# Sheet1.net
KiCad netlist of a schematic drawn in Altium Designer
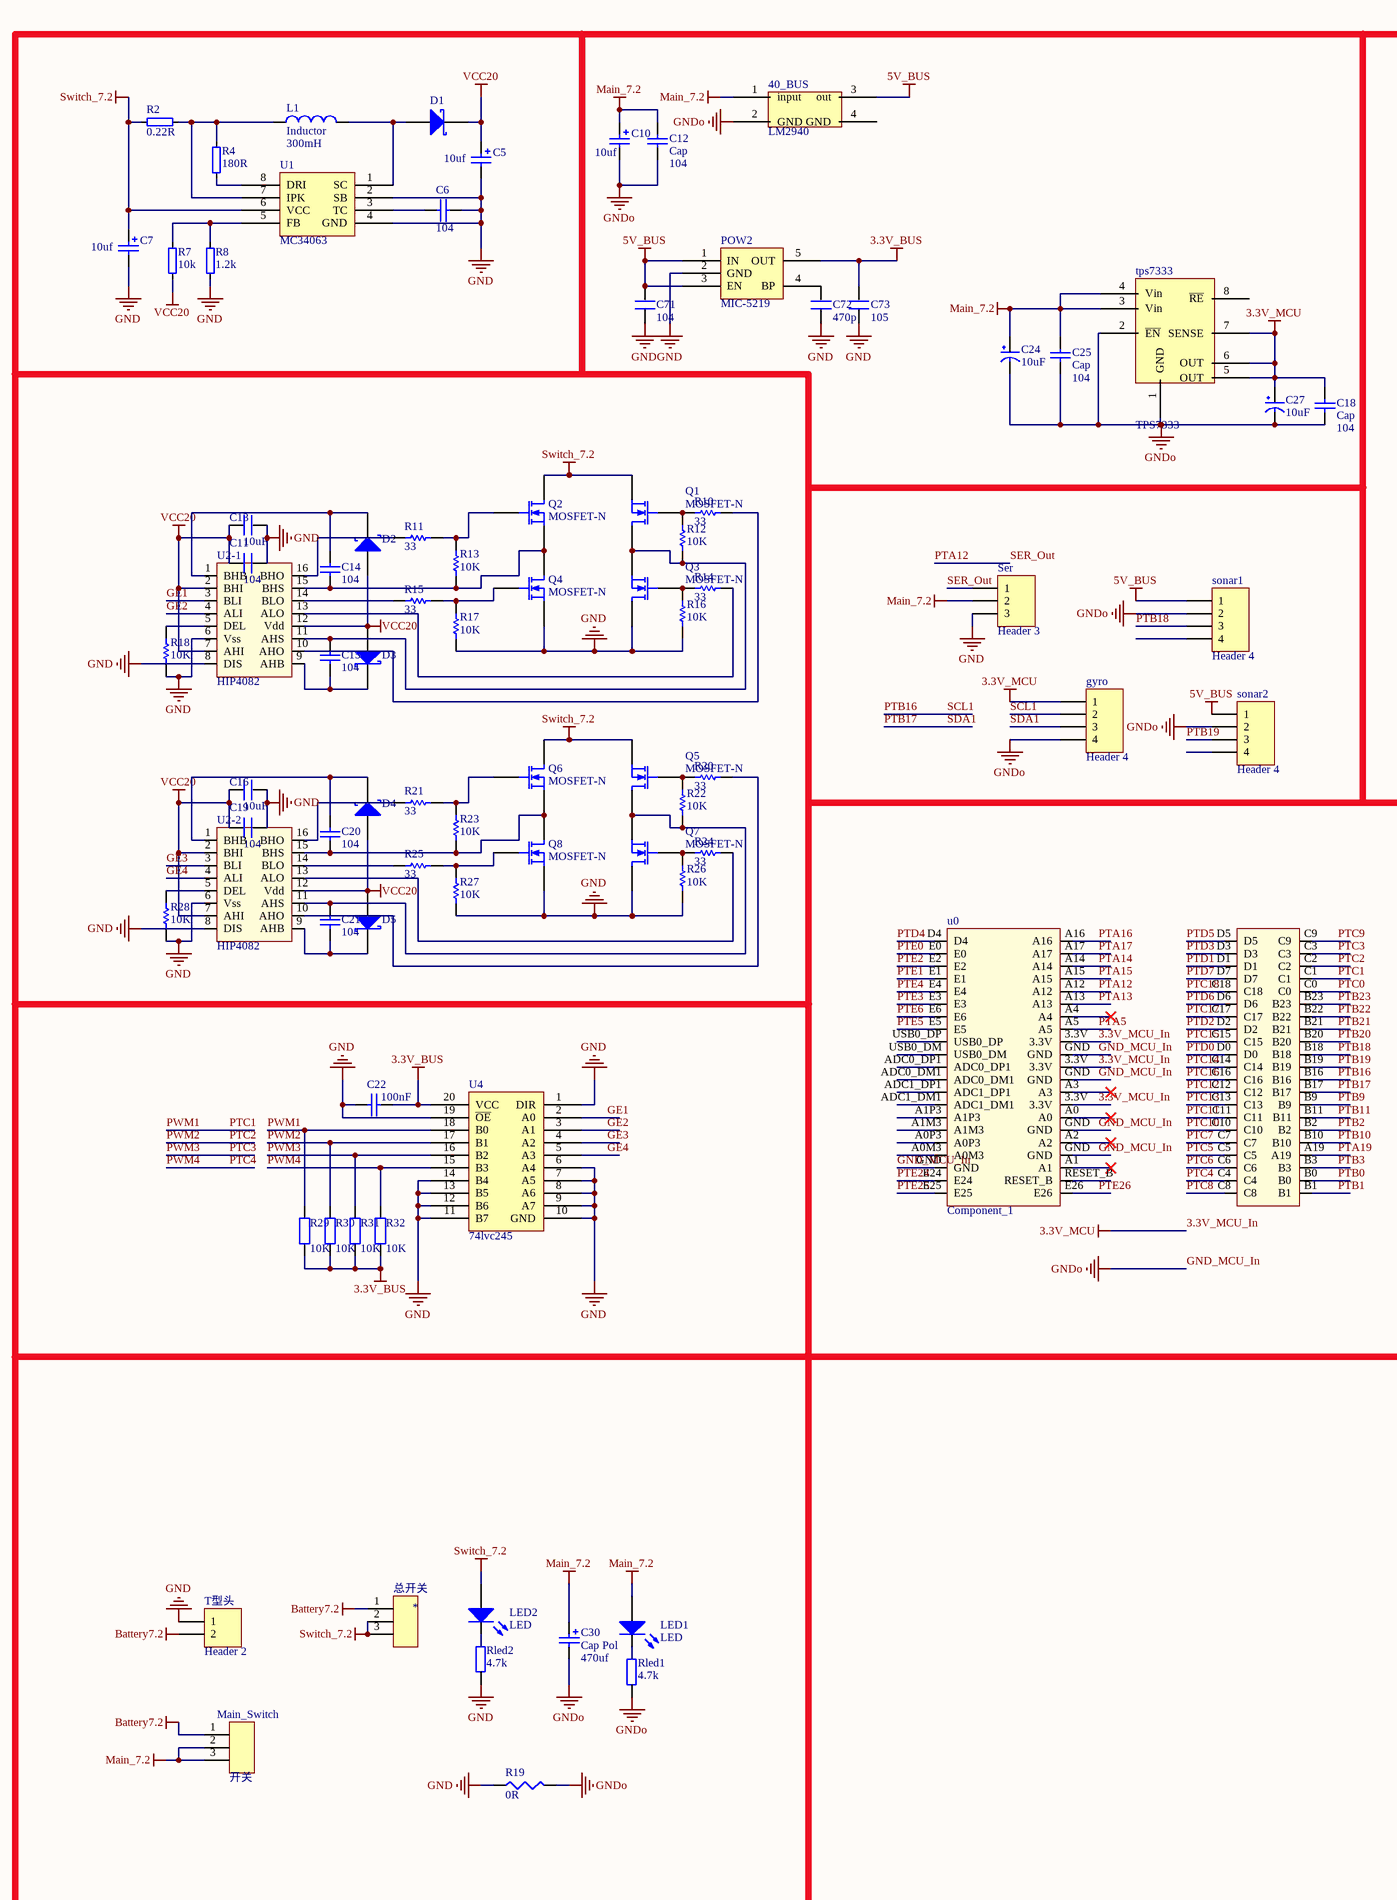
[diagram p0: Sheet1.SchDoc, left]
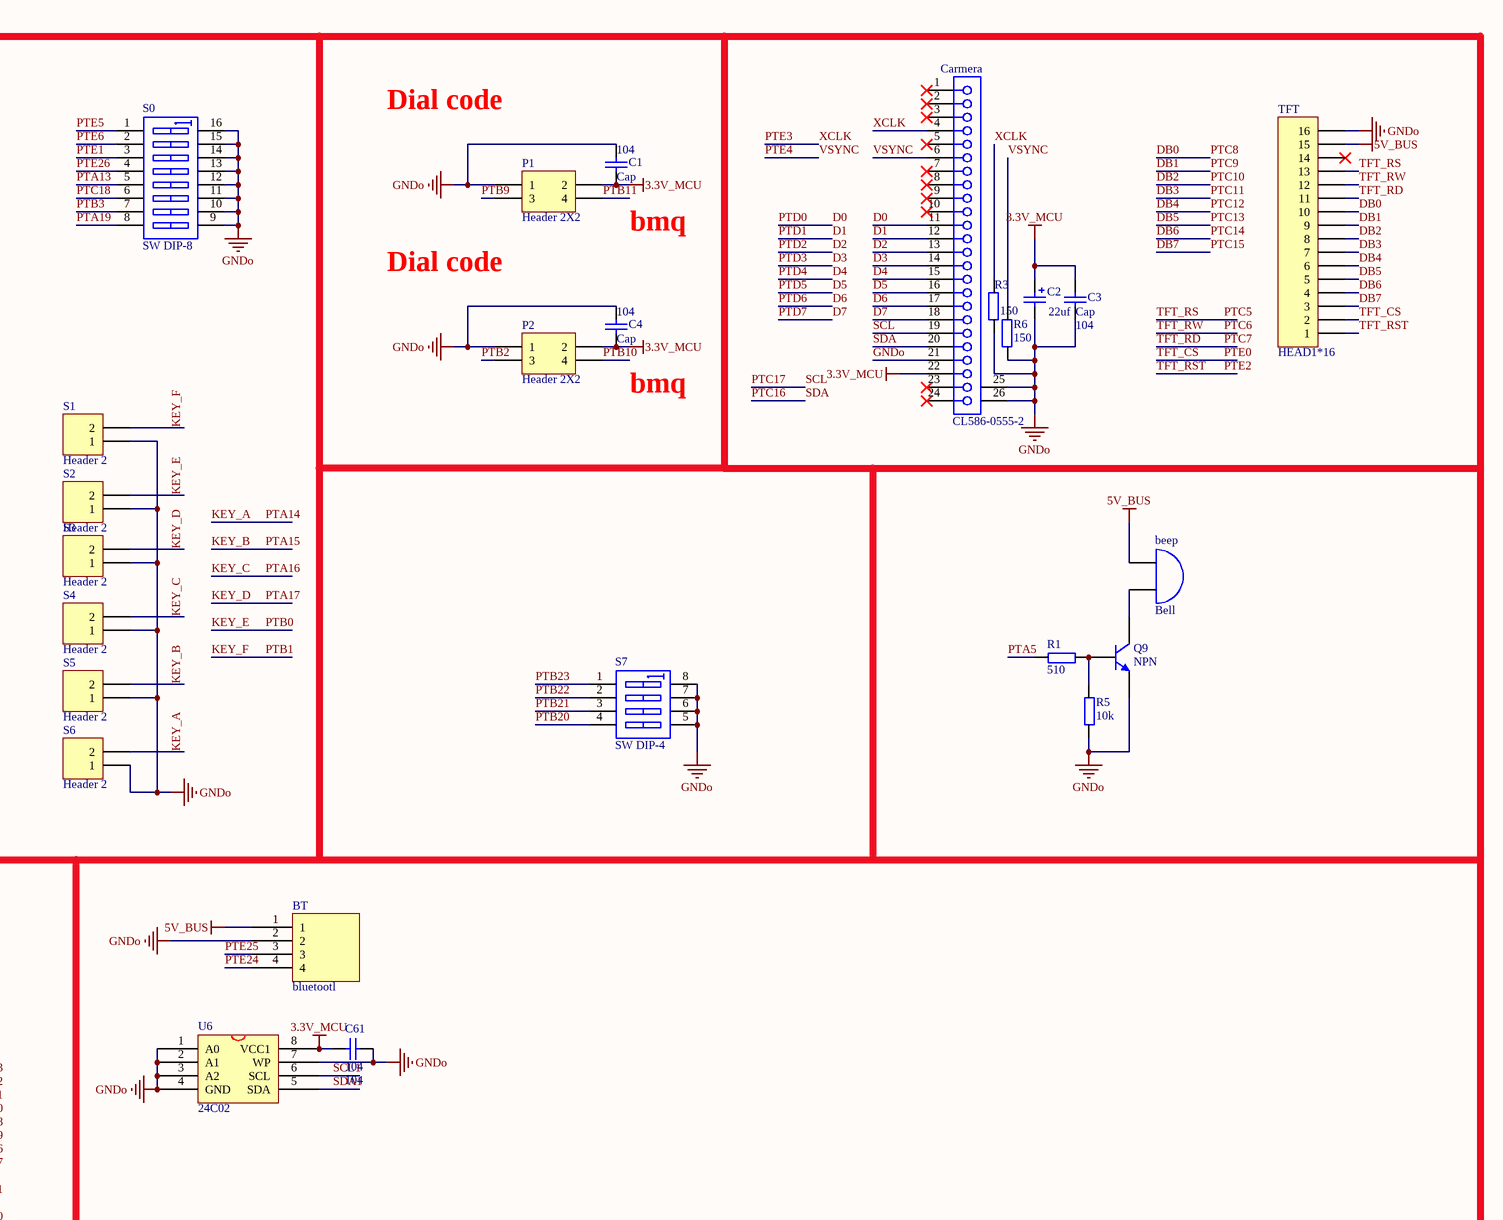
[diagram p1: Sheet1.SchDoc, right]

(export (version "E")
  (design (tool "Eeschema 10.0.6"))
  (components
    (comp (ref "40_BUS") (value "LM2940") (footprint "TO-263-3") (libsource (lib "常用元件") (part "LM2940")))
    (comp (ref "beep")
      (value "Bell")
      (footprint "bell")
      (description "Electrical Bell")
      (fields (field (name "PUBLISHER") "Altium Limited"))
      (libsource (lib "Miscellaneous Devices") (part "Bell"))
    )
    (comp (ref "BT")
      (value "bluetootl")
      (footprint "HDR1X4")
      (description "4 Pin Header")
      (libsource (lib "元件库") (part "USB"))
    )
    (comp (ref "C1")
      (value "Cap")
      (footprint "0805-0C")
      (description "Capacitor")
      (fields (field (name "ALTIUM_VALUE") "104") (field (name "PUBLISHER") "Altium Limited"))
      (libsource (lib "常用元件") (part "Cap"))
    )
    (comp (ref "C2")
      (value "22uf")
      (footprint "3216-A-TA")
      (description "Polarized Capacitor (Radial)")
      (fields (field (name "PUBLISHER") "Altium Limited"))
      (libsource (lib "常用元件") (part "Cap Pol"))
    )
    (comp (ref "C3")
      (value "Cap")
      (footprint "0805-0C")
      (description "Capacitor")
      (fields (field (name "ALTIUM_VALUE") "104") (field (name "PUBLISHER") "Altium Limited"))
      (libsource (lib "常用元件") (part "Cap"))
    )
    (comp (ref "C4")
      (value "Cap")
      (footprint "0805-0C")
      (description "Capacitor")
      (fields (field (name "ALTIUM_VALUE") "104") (field (name "PUBLISHER") "Altium Limited"))
      (libsource (lib "常用元件") (part "Cap"))
    )
    (comp (ref "C5")
      (value "10uf")
      (footprint "3216-A-TA")
      (description "Polarized Capacitor (Radial)")
      (fields (field (name "PUBLISHER") "Altium Limited"))
      (libsource (lib "常用元件") (part "Cap Pol"))
    )
    (comp (ref "C6")
      (value "104")
      (footprint "0805-0C")
      (description "Capacitor")
      (libsource (lib "电容") (part "普通电容"))
    )
    (comp (ref "C7")
      (value "10uf")
      (footprint "3216-A-TA")
      (description "Polarized Capacitor (Radial)")
      (fields (field (name "PUBLISHER") "Altium Limited"))
      (libsource (lib "常用元件") (part "Cap Pol"))
    )
    (comp (ref "C10")
      (value "10uf")
      (footprint "3216-A-TA")
      (description "Polarized Capacitor (Radial)")
      (fields (field (name "PUBLISHER") "Altium Limited"))
      (libsource (lib "常用元件") (part "Cap Pol"))
    )
    (comp (ref "C11") (value "104") (footprint "0805-0C") (libsource (lib "战舰STM32开发板底板封装库") (part "C")))
    (comp (ref "C12")
      (value "Cap")
      (footprint "0805-0C")
      (description "Capacitor")
      (fields (field (name "ALTIUM_VALUE") "104") (field (name "PUBLISHER") "Altium Limited"))
      (libsource (lib "常用元件") (part "Cap"))
    )
    (comp (ref "C13") (value "10uF") (footprint "3216-A-TA") (libsource (lib "战舰STM32开发板底板封装库") (part "C")))
    (comp (ref "C14")
      (value "104")
      (footprint "0805-0C")
      (description "Capacitor")
      (fields (field (name "Comment") "Cap") (field (name "PUBLISHER") "Altium Limited"))
      (libsource (lib "Miscellaneous Devices") (part "Cap"))
    )
    (comp (ref "C15")
      (value "104")
      (footprint "0805-0C")
      (description "Capacitor")
      (fields (field (name "Comment") "Cap") (field (name "PUBLISHER") "Altium Limited"))
      (libsource (lib "Miscellaneous Devices") (part "Cap"))
    )
    (comp (ref "C16") (value "10uF") (footprint "3216-A-TA") (libsource (lib "战舰STM32开发板底板封装库") (part "C")))
    (comp (ref "C18")
      (value "Cap")
      (footprint "0805-0C")
      (description "Capacitor")
      (fields (field (name "ALTIUM_VALUE") "104") (field (name "PUBLISHER") "Altium Limited"))
      (libsource (lib "常用元件") (part "Cap"))
    )
    (comp (ref "C19") (value "104") (footprint "0805-0C") (libsource (lib "战舰STM32开发板底板封装库") (part "C")))
    (comp (ref "C20")
      (value "104")
      (footprint "0805-0C")
      (description "Capacitor")
      (fields (field (name "Comment") "Cap") (field (name "PUBLISHER") "Altium Limited"))
      (libsource (lib "Miscellaneous Devices") (part "Cap"))
    )
    (comp (ref "C21")
      (value "104")
      (footprint "0805-0C")
      (description "Capacitor")
      (fields (field (name "Comment") "Cap") (field (name "PUBLISHER") "Altium Limited"))
      (libsource (lib "Miscellaneous Devices") (part "Cap"))
    )
    (comp (ref "C22")
      (value "100nF")
      (footprint "0603C")
      (description "Capacitor")
      (libsource (lib "MOS motor driving module ") (part "Cap"))
    )
    (comp (ref "C24")
      (value "10uF")
      (footprint "3216-A-TA")
      (description "有极性电容")
      (libsource (lib "原理图库") (part "C"))
    )
    (comp (ref "C25")
      (value "Cap")
      (footprint "0805-0C")
      (description "Capacitor")
      (fields (field (name "ALTIUM_VALUE") "104") (field (name "PUBLISHER") "Altium Limited"))
      (libsource (lib "常用元件集成库") (part "Cap"))
    )
    (comp (ref "C27")
      (value "10uF")
      (footprint "3216-A-TA")
      (description "有极性电容")
      (libsource (lib "原理图库") (part "C"))
    )
    (comp (ref "C30")
      (value "Cap Pol")
      (footprint "C7343")
      (description "Polarized Capacitor (Radial)")
      (fields (field (name "ALTIUM_VALUE") "470uf") (field (name "PUBLISHER") "Altium Limited"))
      (libsource (lib "常用元件") (part "Cap Pol"))
    )
    (comp (ref "C61")
      (value "104")
      (footprint "0603C")
      (description "Capacitor")
      (fields (field (name "ALTIUM_VALUE") "104") (field (name "PUBLISHER") "Altium Limited"))
      (libsource (lib "常用元件集成库") (part "Cap"))
    )
    (comp (ref "C71") (value "104") (footprint "0603P") (libsource (lib "战舰STM32开发板底板封装库") (part "C")))
    (comp (ref "C72") (value "470p") (footprint "0603P") (libsource (lib "战舰STM32开发板底板封装库") (part "C")))
    (comp (ref "C73") (value "105") (footprint "0603P") (libsource (lib "战舰STM32开发板底板封装库") (part "C")))
    (comp (ref "Carmera")
      (value "CL586-0555-2")
      (footprint "FH12A-24S-0.5SH")
      (description "FH12 Series, \"Flip-Lock\" SMT/ZIF FFC/FPC Connector - 0.5mm Spaced Top Contact")
      (fields (field (name "PUBLISHER") "Altium Limited"))
      (libsource (lib "HRS FPC-FFC FH12 Series") (part "CL586-0555-2"))
    )
    (comp (ref "D1")
      (value "D Schottky")
      (footprint "DO-214")
      (description "Schottky Diode")
      (fields (field (name "PUBLISHER") "Altium Limited"))
      (libsource (lib "Miscellaneous Devices") (part "D Schottky"))
    )
    (comp (ref "D2")
      (value "D Schottky")
      (footprint "DO-214")
      (description "Schottky Diode")
      (fields (field (name "PUBLISHER") "Altium Limited"))
      (libsource (lib "Miscellaneous Devices") (part "D Schottky"))
    )
    (comp (ref "D3")
      (value "D Schottky")
      (footprint "DO-214")
      (description "Schottky Diode")
      (fields (field (name "PUBLISHER") "Altium Limited"))
      (libsource (lib "Miscellaneous Devices") (part "D Schottky"))
    )
    (comp (ref "D4")
      (value "D Schottky")
      (footprint "DO-214")
      (description "Schottky Diode")
      (fields (field (name "PUBLISHER") "Altium Limited"))
      (libsource (lib "Miscellaneous Devices") (part "D Schottky"))
    )
    (comp (ref "D5")
      (value "D Schottky")
      (footprint "DO-214")
      (description "Schottky Diode")
      (fields (field (name "PUBLISHER") "Altium Limited"))
      (libsource (lib "Miscellaneous Devices") (part "D Schottky"))
    )
    (comp (ref "gyro")
      (value "Header 4")
      (footprint "HDR1X4")
      (description "Header, 4-Pin")
      (fields (field (name "PUBLISHER") "Altium Limited"))
      (libsource (lib "Miscellaneous Connectors") (part "Header 4"))
    )
    (comp (ref "L1")
      (value "Inductor")
      (footprint "L7X7")
      (fields (field (name "ALTIUM_VALUE") "300mH") (field (name "PUBLISHER") "Altium Limited"))
      (libsource (lib "Miscellaneous Devices") (part "Inductor"))
    )
    (comp (ref "LED1")
      (value "LED")
      (footprint "0805LED2")
      (description "发光二极管")
      (libsource (lib "原理图库") (part "LED"))
    )
    (comp (ref "LED2")
      (value "LED")
      (footprint "0805LED2")
      (description "发光二极管")
      (libsource (lib "原理图库") (part "LED"))
    )
    (comp (ref "Main_Switch") (value "开关") (footprint "乒乓开关5mm") (libsource (lib "常用元件集成库") (part "乒乓开关")))
    (comp (ref "P1")
      (value "Header 2X2")
      (footprint "HDR2X2")
      (description "Header, 2-Pin, Dual row")
      (fields (field (name "PUBLISHER") "Altium Limited"))
      (libsource (lib "Miscellaneous Connectors") (part "Header 2X2"))
    )
    (comp (ref "P2")
      (value "Header 2X2")
      (footprint "HDR2X2")
      (description "Header, 2-Pin, Dual row")
      (fields (field (name "PUBLISHER") "Altium Limited"))
      (libsource (lib "Miscellaneous Connectors") (part "Header 2X2"))
    )
    (comp (ref "POW2") (value "MIC-5219") (footprint "sot23-5") (libsource (lib "mic5219") (part "MIC-5219")))
    (comp (ref "Q1")
      (value "MOSFET-N")
      (footprint "to252")
      (description "N-Channel MOSFET")
      (fields (field (name "PUBLISHER") "Altium Limited"))
      (libsource (lib "Miscellaneous Devices") (part "MOSFET-N"))
    )
    (comp (ref "Q2")
      (value "MOSFET-N")
      (footprint "to252")
      (description "N-Channel MOSFET")
      (fields (field (name "PUBLISHER") "Altium Limited"))
      (libsource (lib "Miscellaneous Devices") (part "MOSFET-N"))
    )
    (comp (ref "Q3")
      (value "MOSFET-N")
      (footprint "to252")
      (description "N-Channel MOSFET")
      (fields (field (name "PUBLISHER") "Altium Limited"))
      (libsource (lib "Miscellaneous Devices") (part "MOSFET-N"))
    )
    (comp (ref "Q4")
      (value "MOSFET-N")
      (footprint "to252")
      (description "N-Channel MOSFET")
      (fields (field (name "PUBLISHER") "Altium Limited"))
      (libsource (lib "Miscellaneous Devices") (part "MOSFET-N"))
    )
    (comp (ref "Q5")
      (value "MOSFET-N")
      (footprint "to252")
      (description "N-Channel MOSFET")
      (fields (field (name "PUBLISHER") "Altium Limited"))
      (libsource (lib "Miscellaneous Devices") (part "MOSFET-N"))
    )
    (comp (ref "Q6")
      (value "MOSFET-N")
      (footprint "to252")
      (description "N-Channel MOSFET")
      (fields (field (name "PUBLISHER") "Altium Limited"))
      (libsource (lib "Miscellaneous Devices") (part "MOSFET-N"))
    )
    (comp (ref "Q7")
      (value "MOSFET-N")
      (footprint "to252")
      (description "N-Channel MOSFET")
      (fields (field (name "PUBLISHER") "Altium Limited"))
      (libsource (lib "Miscellaneous Devices") (part "MOSFET-N"))
    )
    (comp (ref "Q8")
      (value "MOSFET-N")
      (footprint "to252")
      (description "N-Channel MOSFET")
      (fields (field (name "PUBLISHER") "Altium Limited"))
      (libsource (lib "Miscellaneous Devices") (part "MOSFET-N"))
    )
    (comp (ref "Q9")
      (value "NPN")
      (footprint "TO-226-AA")
      (description "NPN Bipolar Transistor")
      (fields (field (name "PUBLISHER") "Altium Limited"))
      (libsource (lib "Miscellaneous Devices") (part "NPN"))
    )
    (comp (ref "R1") (value "510") (footprint "0805-0R") (libsource (lib "原理图库") (part "Res")))
    (comp (ref "R2") (value "0.22R") (footprint "0805-0R") (libsource (lib "电阻") (part "RES")))
    (comp (ref "R3") (value "150") (footprint "0805-0R") (libsource (lib "原理图库") (part "Res")))
    (comp (ref "R4") (value "180R") (footprint "0805-0R") (libsource (lib "电阻") (part "RES")))
    (comp (ref "R5") (value "10k") (footprint "0805-0r") (libsource (lib "原理图库") (part "Res")))
    (comp (ref "R6") (value "150") (footprint "0805-0R") (libsource (lib "原理图库") (part "Res")))
    (comp (ref "R7") (value "10k") (footprint "0805-0R") (libsource (lib "电阻") (part "RES")))
    (comp (ref "R8") (value "1.2k") (footprint "0805-0R") (libsource (lib "电阻") (part "RES")))
    (comp (ref "R10")
      (value "33")
      (footprint "0805-0R")
      (description "Resistor")
      (fields (field (name "Comment") "Res1") (field (name "PUBLISHER") "Altium Limited"))
      (libsource (lib "Miscellaneous Devices") (part "Res1"))
    )
    (comp (ref "R11")
      (value "33")
      (footprint "0805-0R")
      (description "Resistor")
      (fields (field (name "Comment") "Res1") (field (name "PUBLISHER") "Altium Limited"))
      (libsource (lib "Miscellaneous Devices") (part "Res1"))
    )
    (comp (ref "R12")
      (value "10K")
      (footprint "0805-0R")
      (description "Resistor")
      (fields (field (name "Comment") "Res1") (field (name "PUBLISHER") "Altium Limited"))
      (libsource (lib "Miscellaneous Devices") (part "Res1"))
    )
    (comp (ref "R13")
      (value "10K")
      (footprint "0805-0R")
      (description "Resistor")
      (fields (field (name "Comment") "Res1") (field (name "PUBLISHER") "Altium Limited"))
      (libsource (lib "Miscellaneous Devices") (part "Res1"))
    )
    (comp (ref "R14")
      (value "33")
      (footprint "0805-0R")
      (description "Resistor")
      (fields (field (name "Comment") "Res1") (field (name "PUBLISHER") "Altium Limited"))
      (libsource (lib "Miscellaneous Devices") (part "Res1"))
    )
    (comp (ref "R15")
      (value "33")
      (footprint "0805-0R")
      (description "Resistor")
      (fields (field (name "Comment") "Res1") (field (name "PUBLISHER") "Altium Limited"))
      (libsource (lib "Miscellaneous Devices") (part "Res1"))
    )
    (comp (ref "R16")
      (value "10K")
      (footprint "0805-0R")
      (description "Resistor")
      (fields (field (name "Comment") "Res1") (field (name "PUBLISHER") "Altium Limited"))
      (libsource (lib "Miscellaneous Devices") (part "Res1"))
    )
    (comp (ref "R17")
      (value "10K")
      (footprint "0805-0R")
      (description "Resistor")
      (fields (field (name "Comment") "Res1") (field (name "PUBLISHER") "Altium Limited"))
      (libsource (lib "Miscellaneous Devices") (part "Res1"))
    )
    (comp (ref "R18")
      (value "10K")
      (footprint "0805-0R")
      (description "Resistor")
      (fields (field (name "Comment") "Res1") (field (name "PUBLISHER") "Altium Limited"))
      (libsource (lib "Miscellaneous Devices") (part "Res1"))
    )
    (comp (ref "R19")
      (value "0R")
      (footprint "0805-0R")
      (description "Resistor")
      (fields (field (name "Comment") "Res") (field (name "PUBLISHER") "Altium Limited"))
      (libsource (lib "常用元件") (part "Res"))
    )
    (comp (ref "R20")
      (value "33")
      (footprint "0805-0R")
      (description "Resistor")
      (fields (field (name "Comment") "Res1") (field (name "PUBLISHER") "Altium Limited"))
      (libsource (lib "Miscellaneous Devices") (part "Res1"))
    )
    (comp (ref "R21")
      (value "33")
      (footprint "0805-0R")
      (description "Resistor")
      (fields (field (name "Comment") "Res1") (field (name "PUBLISHER") "Altium Limited"))
      (libsource (lib "Miscellaneous Devices") (part "Res1"))
    )
    (comp (ref "R22")
      (value "10K")
      (footprint "0805-0R")
      (description "Resistor")
      (fields (field (name "Comment") "Res1") (field (name "PUBLISHER") "Altium Limited"))
      (libsource (lib "Miscellaneous Devices") (part "Res1"))
    )
    (comp (ref "R23")
      (value "10K")
      (footprint "0805-0R")
      (description "Resistor")
      (fields (field (name "Comment") "Res1") (field (name "PUBLISHER") "Altium Limited"))
      (libsource (lib "Miscellaneous Devices") (part "Res1"))
    )
    (comp (ref "R24")
      (value "33")
      (footprint "0805-0R")
      (description "Resistor")
      (fields (field (name "Comment") "Res1") (field (name "PUBLISHER") "Altium Limited"))
      (libsource (lib "Miscellaneous Devices") (part "Res1"))
    )
    (comp (ref "R25")
      (value "33")
      (footprint "0805-0R")
      (description "Resistor")
      (fields (field (name "Comment") "Res1") (field (name "PUBLISHER") "Altium Limited"))
      (libsource (lib "Miscellaneous Devices") (part "Res1"))
    )
    (comp (ref "R26")
      (value "10K")
      (footprint "0805-0R")
      (description "Resistor")
      (fields (field (name "Comment") "Res1") (field (name "PUBLISHER") "Altium Limited"))
      (libsource (lib "Miscellaneous Devices") (part "Res1"))
    )
    (comp (ref "R27")
      (value "10K")
      (footprint "0805-0R")
      (description "Resistor")
      (fields (field (name "Comment") "Res1") (field (name "PUBLISHER") "Altium Limited"))
      (libsource (lib "Miscellaneous Devices") (part "Res1"))
    )
    (comp (ref "R28")
      (value "10K")
      (footprint "0805-0R")
      (description "Resistor")
      (fields (field (name "Comment") "Res1") (field (name "PUBLISHER") "Altium Limited"))
      (libsource (lib "Miscellaneous Devices") (part "Res1"))
    )
    (comp (ref "R29")
      (value "10K")
      (footprint "0603R")
      (description "Resistor")
      (fields (field (name "Comment") "Res2") (field (name "PUBLISHER") "Altium Limited"))
      (libsource (lib "MOS motor driving module ") (part "Res2"))
    )
    (comp (ref "R30")
      (value "10K")
      (footprint "0603R")
      (description "Resistor")
      (fields (field (name "Comment") "Res2") (field (name "PUBLISHER") "Altium Limited"))
      (libsource (lib "MOS motor driving module ") (part "Res2"))
    )
    (comp (ref "R31")
      (value "10K")
      (footprint "0603R")
      (description "Resistor")
      (fields (field (name "Comment") "Res2") (field (name "PUBLISHER") "Altium Limited"))
      (libsource (lib "MOS motor driving module ") (part "Res2"))
    )
    (comp (ref "R32")
      (value "10K")
      (footprint "0603R")
      (description "Resistor")
      (fields (field (name "Comment") "Res2") (field (name "PUBLISHER") "Altium Limited"))
      (libsource (lib "MOS motor driving module ") (part "Res2"))
    )
    (comp (ref "Rled1") (value "4.7k") (footprint "0805-0R") (libsource (lib "原理图库") (part "Res")))
    (comp (ref "Rled2") (value "4.7k") (footprint "0805-0R") (libsource (lib "原理图库") (part "Res")))
    (comp (ref "S0")
      (value "SW DIP-8")
      (footprint "SW-DIP8")
      (description "DIP Switch")
      (libsource (lib "元件库") (part "SW DIP-8"))
    )
    (comp (ref "S1")
      (value "Header 2")
      (footprint "SW-SMD1")
      (description "Header, 2-Pin")
      (fields (field (name "PUBLISHER") "Altium Limited"))
      (libsource (lib "Miscellaneous Connectors") (part "Header 2"))
    )
    (comp (ref "S2")
      (value "Header 2")
      (footprint "SW-SMD1")
      (description "Header, 2-Pin")
      (fields (field (name "PUBLISHER") "Altium Limited"))
      (libsource (lib "Miscellaneous Connectors") (part "Header 2"))
    )
    (comp (ref "S3")
      (value "Header 2")
      (footprint "SW-SMD1")
      (description "Header, 2-Pin")
      (fields (field (name "PUBLISHER") "Altium Limited"))
      (libsource (lib "Miscellaneous Connectors") (part "Header 2"))
    )
    (comp (ref "S4")
      (value "Header 2")
      (footprint "SW-SMD1")
      (description "Header, 2-Pin")
      (fields (field (name "PUBLISHER") "Altium Limited"))
      (libsource (lib "Miscellaneous Connectors") (part "Header 2"))
    )
    (comp (ref "S5")
      (value "Header 2")
      (footprint "SW-SMD1")
      (description "Header, 2-Pin")
      (fields (field (name "PUBLISHER") "Altium Limited"))
      (libsource (lib "Miscellaneous Connectors") (part "Header 2"))
    )
    (comp (ref "S6")
      (value "Header 2")
      (footprint "SW-SMD1")
      (description "Header, 2-Pin")
      (fields (field (name "PUBLISHER") "Altium Limited"))
      (libsource (lib "Miscellaneous Connectors") (part "Header 2"))
    )
    (comp (ref "S7")
      (value "SW DIP-4")
      (footprint "DIP-8")
      (description "DIP Switch")
      (libsource (lib "元件库") (part "SW DIP-4"))
    )
    (comp (ref "Ser")
      (value "Header 3")
      (footprint "HDR1X3")
      (description "Header, 3-Pin")
      (fields (field (name "PUBLISHER") "Altium Limited"))
      (libsource (lib "Miscellaneous Connectors") (part "Header 3"))
    )
    (comp (ref "sonar1")
      (value "Header 4")
      (footprint "HDR1X4")
      (description "Header, 4-Pin")
      (fields (field (name "PUBLISHER") "Altium Limited"))
      (libsource (lib "Miscellaneous Connectors") (part "Header 4"))
    )
    (comp (ref "sonar2")
      (value "Header 4")
      (footprint "HDR1X4")
      (description "Header, 4-Pin")
      (fields (field (name "PUBLISHER") "Altium Limited"))
      (libsource (lib "Miscellaneous Connectors") (part "Header 4"))
    )
    (comp (ref "TFT")
      (value "HEAD1*16")
      (footprint "HDR1X16")
      (description "Header, 16-Pin")
      (fields (field (name "PUBLISHER") "Altium Limited"))
      (libsource (lib "EXPLORER") (part "Header 16"))
    )
    (comp (ref "tps7333") (value "TPS7333") (footprint "sop8") (libsource (lib "常用元件") (part "TPS7333")))
    (comp (ref "T型头")
      (value "Header 2")
      (footprint "T HEAD")
      (description "Header, 2-Pin")
      (fields (field (name "PUBLISHER") "Altium Limited"))
      (libsource (lib "") (part "Header 2_1"))
    )
    (comp (ref "u0")
      (value "Component_1")
      (footprint "K60_100")
      (libsource (lib "K60_100") (part "Component_1"))
    )
    (comp (ref "U1") (value "MC34063") (footprint "sop8") (libsource (lib "MC34063") (part "Component_1")))
    (comp (ref "U2-1")
      (value "HIP4082")
      (footprint "SOP-16")
      (libsource (lib "HIP4082") (part "Component_1"))
    )
    (comp (ref "U2-2")
      (value "HIP4082")
      (footprint "SOP-16")
      (libsource (lib "HIP4082") (part "Component_1"))
    )
    (comp (ref "U4") (value "74lvc245") (footprint "TSSOP20") (libsource (lib "74lvc245") (part "74lvc245")))
    (comp (ref "U6") (value "24C02") (footprint "SOP8") (libsource (lib "EXPLORER") (part "24C256")))
    (comp (ref "总开关") (value "*") (footprint "乒乓开关5mm") (libsource (lib "常用元件集成库") (part "乒乓开关")))
  )
  (nets
    (net (code "1") (name "/D0") (class "Default")
      (node (ref "Carmera") (pin "11") (pinfunction "11_11") (pintype "passive"))
      (node (ref "u0") (pin "D0") (pinfunction "D0_D0") (pintype "passive"))
    )
    (net (code "2") (name "/D1") (class "Default")
      (node (ref "Carmera") (pin "12") (pinfunction "12_12") (pintype "passive"))
      (node (ref "u0") (pin "D1") (pinfunction "D1_D1") (pintype "passive"))
    )
    (net (code "3") (name "/D2") (class "Default")
      (node (ref "Carmera") (pin "13") (pinfunction "13_13") (pintype "passive"))
      (node (ref "u0") (pin "D2") (pinfunction "D2_D2") (pintype "passive"))
    )
    (net (code "4") (name "/D3") (class "Default")
      (node (ref "Carmera") (pin "14") (pinfunction "14_14") (pintype "passive"))
      (node (ref "u0") (pin "D3") (pinfunction "D3_D3") (pintype "passive"))
    )
    (net (code "5") (name "/D4") (class "Default")
      (node (ref "Carmera") (pin "15") (pinfunction "15_15") (pintype "passive"))
      (node (ref "u0") (pin "D4") (pinfunction "D4_D4") (pintype "passive"))
    )
    (net (code "6") (name "/D5") (class "Default")
      (node (ref "Carmera") (pin "16") (pinfunction "16_16") (pintype "passive"))
      (node (ref "u0") (pin "D5") (pinfunction "D5_D5") (pintype "passive"))
    )
    (net (code "7") (name "/D6") (class "Default")
      (node (ref "Carmera") (pin "17") (pinfunction "17_17") (pintype "passive"))
      (node (ref "u0") (pin "D6") (pinfunction "D6_D6") (pintype "passive"))
    )
    (net (code "8") (name "/D7") (class "Default")
      (node (ref "Carmera") (pin "18") (pinfunction "18_18") (pintype "passive"))
      (node (ref "u0") (pin "D7") (pinfunction "D7_D7") (pintype "passive"))
    )
    (net (code "9") (name "/DB0") (class "Default")
      (node (ref "TFT") (pin "10") (pinfunction "10_10") (pintype "passive"))
      (node (ref "u0") (pin "C8") (pinfunction "C8_C8") (pintype "passive"))
    )
    (net (code "10") (name "/DB1") (class "Default")
      (node (ref "TFT") (pin "9") (pinfunction "9_9") (pintype "passive"))
      (node (ref "u0") (pin "C9") (pinfunction "C9_C9") (pintype "passive"))
    )
    (net (code "11") (name "/DB2") (class "Default")
      (node (ref "TFT") (pin "8") (pinfunction "8_8") (pintype "passive"))
      (node (ref "u0") (pin "C10") (pinfunction "C10_C10") (pintype "passive"))
    )
    (net (code "12") (name "/DB3") (class "Default")
      (node (ref "TFT") (pin "7") (pinfunction "7_7") (pintype "passive"))
      (node (ref "u0") (pin "C11") (pinfunction "C11_C11") (pintype "passive"))
    )
    (net (code "13") (name "/DB4") (class "Default")
      (node (ref "TFT") (pin "6") (pinfunction "6_6") (pintype "passive"))
      (node (ref "u0") (pin "C12") (pinfunction "C12_C12") (pintype "passive"))
    )
    (net (code "14") (name "/DB5") (class "Default")
      (node (ref "TFT") (pin "5") (pinfunction "5_5") (pintype "passive"))
      (node (ref "u0") (pin "C13") (pinfunction "C13_C13") (pintype "passive"))
    )
    (net (code "15") (name "/DB6") (class "Default")
      (node (ref "TFT") (pin "4") (pinfunction "4_4") (pintype "passive"))
      (node (ref "u0") (pin "C14") (pinfunction "C14_C14") (pintype "passive"))
    )
    (net (code "16") (name "/DB7") (class "Default")
      (node (ref "TFT") (pin "3") (pinfunction "3_3") (pintype "passive"))
      (node (ref "u0") (pin "C15") (pinfunction "C15_C15") (pintype "passive"))
    )
    (net (code "17") (name "/GE1") (class "Default")
      (node (ref "U2-1") (pin "3") (pinfunction "BLI_3") (pintype "passive"))
      (node (ref "U4") (pin "2") (pinfunction "A0_2") (pintype "passive"))
    )
    (net (code "18") (name "/GE2") (class "Default")
      (node (ref "U2-1") (pin "4") (pinfunction "ALI_4") (pintype "passive"))
      (node (ref "U4") (pin "3") (pinfunction "A1_3") (pintype "passive"))
    )
    (net (code "19") (name "/GE3") (class "Default")
      (node (ref "U2-2") (pin "3") (pinfunction "BLI_3") (pintype "passive"))
      (node (ref "U4") (pin "4") (pinfunction "A2_4") (pintype "passive"))
    )
    (net (code "20") (name "/GE4") (class "Default")
      (node (ref "U2-2") (pin "4") (pinfunction "ALI_4") (pintype "passive"))
      (node (ref "U4") (pin "5") (pinfunction "A3_5") (pintype "passive"))
    )
    (net (code "21") (name "/KEY_A") (class "Default")
      (node (ref "S6") (pin "2") (pinfunction "2_2") (pintype "passive"))
      (node (ref "u0") (pin "A14") (pinfunction "A14_A14") (pintype "passive"))
    )
    (net (code "22") (name "/KEY_B") (class "Default")
      (node (ref "S5") (pin "2") (pinfunction "2_2") (pintype "passive"))
      (node (ref "u0") (pin "A15") (pinfunction "A15_A15") (pintype "passive"))
    )
    (net (code "23") (name "/KEY_C") (class "Default")
      (node (ref "S4") (pin "2") (pinfunction "2_2") (pintype "passive"))
      (node (ref "u0") (pin "A16") (pinfunction "A16_A16") (pintype "passive"))
    )
    (net (code "24") (name "/KEY_D") (class "Default")
      (node (ref "S3") (pin "2") (pinfunction "2_2") (pintype "passive"))
      (node (ref "u0") (pin "A17") (pinfunction "A17_A17") (pintype "passive"))
    )
    (net (code "25") (name "/KEY_E") (class "Default")
      (node (ref "S2") (pin "2") (pinfunction "2_2") (pintype "passive"))
      (node (ref "u0") (pin "B0") (pinfunction "B0_B0") (pintype "passive"))
    )
    (net (code "26") (name "/KEY_F") (class "Default")
      (node (ref "S1") (pin "2") (pinfunction "2_2") (pintype "passive"))
      (node (ref "u0") (pin "B1") (pinfunction "B1_B1") (pintype "passive"))
    )
    (net (code "27") (name "/PTA5") (class "Default")
      (node (ref "R1") (pin "1") (pintype "passive"))
      (node (ref "u0") (pin "A5") (pinfunction "A5_A5") (pintype "passive"))
    )
    (net (code "28") (name "/PTA12") (class "Default")
      (node (ref "Ser") (pin "1") (pinfunction "1_1") (pintype "passive"))
      (node (ref "u0") (pin "A12") (pinfunction "A12_A12") (pintype "passive"))
    )
    (net (code "29") (name "/PTA13") (class "Default")
      (node (ref "S0") (pin "5") (pinfunction "A5_5") (pintype "passive"))
      (node (ref "u0") (pin "A13") (pinfunction "A13_A13") (pintype "passive"))
    )
    (net (code "30") (name "/PTA19") (class "Default")
      (node (ref "S0") (pin "8") (pinfunction "A8_8") (pintype "passive"))
      (node (ref "u0") (pin "A19") (pinfunction "A19_A19") (pintype "passive"))
    )
    (net (code "31") (name "/PTB2") (class "Default")
      (node (ref "P2") (pin "3") (pinfunction "3_3") (pintype "passive"))
      (node (ref "u0") (pin "B2") (pinfunction "B2_B2") (pintype "passive"))
    )
    (net (code "32") (name "/PTB3") (class "Default")
      (node (ref "S0") (pin "7") (pinfunction "A7_7") (pintype "passive"))
      (node (ref "u0") (pin "B3") (pinfunction "B3_B3") (pintype "passive"))
    )
    (net (code "33") (name "/PTB9") (class "Default")
      (node (ref "P1") (pin "3") (pinfunction "3_3") (pintype "passive"))
      (node (ref "u0") (pin "B9") (pinfunction "B9_B9") (pintype "passive"))
    )
    (net (code "34") (name "/PTB10") (class "Default")
      (node (ref "P2") (pin "4") (pinfunction "4_4") (pintype "passive"))
      (node (ref "u0") (pin "B10") (pinfunction "B10_B10") (pintype "passive"))
    )
    (net (code "35") (name "/PTB11") (class "Default")
      (node (ref "P1") (pin "4") (pinfunction "4_4") (pintype "passive"))
      (node (ref "u0") (pin "B11") (pinfunction "B11_B11") (pintype "passive"))
    )
    (net (code "36") (name "/PTB16") (class "Default")
      (node (ref "U6") (pin "6") (pinfunction "SCL_6") (pintype "passive"))
      (node (ref "gyro") (pin "2") (pinfunction "2_2") (pintype "passive"))
      (node (ref "u0") (pin "B16") (pinfunction "B16_B16") (pintype "passive"))
    )
    (net (code "37") (name "/PTB17") (class "Default")
      (node (ref "U6") (pin "5") (pinfunction "SDA_5") (pintype "passive"))
      (node (ref "gyro") (pin "3") (pinfunction "3_3") (pintype "passive"))
      (node (ref "u0") (pin "B17") (pinfunction "B17_B17") (pintype "passive"))
    )
    (net (code "38") (name "/PTB18") (class "Default")
      (node (ref "sonar1") (pin "3") (pinfunction "3_3") (pintype "passive"))
      (node (ref "u0") (pin "B18") (pinfunction "B18_B18") (pintype "passive"))
    )
    (net (code "39") (name "/PTB19") (class "Default")
      (node (ref "sonar2") (pin "3") (pinfunction "3_3") (pintype "passive"))
      (node (ref "u0") (pin "B19") (pinfunction "B19_B19") (pintype "passive"))
    )
    (net (code "40") (name "/PTB20") (class "Default")
      (node (ref "S7") (pin "4") (pinfunction "A4_4") (pintype "passive"))
      (node (ref "u0") (pin "B20") (pinfunction "B20_B20") (pintype "passive"))
    )
    (net (code "41") (name "/PTB21") (class "Default")
      (node (ref "S7") (pin "3") (pinfunction "A3_3") (pintype "passive"))
      (node (ref "u0") (pin "B21") (pinfunction "B21_B21") (pintype "passive"))
    )
    (net (code "42") (name "/PTB22") (class "Default")
      (node (ref "S7") (pin "2") (pinfunction "A2_2") (pintype "passive"))
      (node (ref "u0") (pin "B22") (pinfunction "B22_B22") (pintype "passive"))
    )
    (net (code "43") (name "/PTB23") (class "Default")
      (node (ref "S7") (pin "1") (pinfunction "A1_1") (pintype "passive"))
      (node (ref "u0") (pin "B23") (pinfunction "B23_B23") (pintype "passive"))
    )
    (net (code "44") (name "/PTC0") (class "Default")
      (node (ref "u0") (pin "C0") (pinfunction "C0_C0") (pintype "passive"))
    )
    (net (code "45") (name "/PTC1") (class "Default")
      (node (ref "R29") (pin "2") (pinfunction "2_2") (pintype "passive"))
      (node (ref "U4") (pin "18") (pinfunction "B0_18") (pintype "passive"))
      (node (ref "u0") (pin "C1") (pinfunction "C1_C1") (pintype "passive"))
    )
    (net (code "46") (name "/PTC2") (class "Default")
      (node (ref "R30") (pin "2") (pinfunction "2_2") (pintype "passive"))
      (node (ref "U4") (pin "17") (pinfunction "B1_17") (pintype "passive"))
      (node (ref "u0") (pin "C2") (pinfunction "C2_C2") (pintype "passive"))
    )
    (net (code "47") (name "/PTC3") (class "Default")
      (node (ref "R31") (pin "2") (pinfunction "2_2") (pintype "passive"))
      (node (ref "U4") (pin "16") (pinfunction "B2_16") (pintype "passive"))
      (node (ref "u0") (pin "C3") (pinfunction "C3_C3") (pintype "passive"))
    )
    (net (code "48") (name "/PTC4") (class "Default")
      (node (ref "R32") (pin "2") (pinfunction "2_2") (pintype "passive"))
      (node (ref "U4") (pin "15") (pinfunction "B3_15") (pintype "passive"))
      (node (ref "u0") (pin "C4") (pinfunction "C4_C4") (pintype "passive"))
    )
    (net (code "49") (name "/PTC5") (class "Default")
      (node (ref "TFT") (pin "13") (pinfunction "13_13") (pintype "passive"))
      (node (ref "u0") (pin "C5") (pinfunction "C5_C5") (pintype "passive"))
    )
    (net (code "50") (name "/PTC6") (class "Default")
      (node (ref "TFT") (pin "12") (pinfunction "12_12") (pintype "passive"))
      (node (ref "u0") (pin "C6") (pinfunction "C6_C6") (pintype "passive"))
    )
    (net (code "51") (name "/PTC7") (class "Default")
      (node (ref "TFT") (pin "11") (pinfunction "11_11") (pintype "passive"))
      (node (ref "u0") (pin "C7") (pinfunction "C7_C7") (pintype "passive"))
    )
    (net (code "52") (name "/PTC16") (class "Default")
      (node (ref "Carmera") (pin "20") (pinfunction "20_20") (pintype "passive"))
      (node (ref "u0") (pin "C16") (pinfunction "C16_C16") (pintype "passive"))
    )
    (net (code "53") (name "/PTC17") (class "Default")
      (node (ref "Carmera") (pin "19") (pinfunction "19_19") (pintype "passive"))
      (node (ref "u0") (pin "C17") (pinfunction "C17_C17") (pintype "passive"))
    )
    (net (code "54") (name "/PTC18") (class "Default")
      (node (ref "S0") (pin "6") (pinfunction "A6_6") (pintype "passive"))
      (node (ref "u0") (pin "C18") (pinfunction "C18_C18") (pintype "passive"))
    )
    (net (code "55") (name "/PTE0") (class "Default")
      (node (ref "TFT") (pin "2") (pinfunction "2_2") (pintype "passive"))
      (node (ref "u0") (pin "E0") (pinfunction "E0_E0") (pintype "passive"))
    )
    (net (code "56") (name "/PTE1") (class "Default")
      (node (ref "S0") (pin "3") (pinfunction "A3_3") (pintype "passive"))
      (node (ref "u0") (pin "E1") (pinfunction "E1_E1") (pintype "passive"))
    )
    (net (code "57") (name "/PTE2") (class "Default")
      (node (ref "TFT") (pin "1") (pinfunction "1_1") (pintype "passive"))
      (node (ref "u0") (pin "E2") (pinfunction "E2_E2") (pintype "passive"))
    )
    (net (code "58") (name "/PTE3") (class "Default")
      (node (ref "Carmera") (pin "4") (pinfunction "4_4") (pintype "passive"))
      (node (ref "R3") (pin "1") (pintype "passive"))
      (node (ref "u0") (pin "E3") (pinfunction "E3_E3") (pintype "passive"))
    )
    (net (code "59") (name "/PTE4") (class "Default")
      (node (ref "Carmera") (pin "6") (pinfunction "6_6") (pintype "passive"))
      (node (ref "R6") (pin "1") (pintype "passive"))
      (node (ref "u0") (pin "E4") (pinfunction "E4_E4") (pintype "passive"))
    )
    (net (code "60") (name "/PTE5") (class "Default")
      (node (ref "S0") (pin "1") (pinfunction "A1_1") (pintype "passive"))
      (node (ref "u0") (pin "E5") (pinfunction "E5_E5") (pintype "passive"))
    )
    (net (code "61") (name "/PTE6") (class "Default")
      (node (ref "S0") (pin "2") (pinfunction "A2_2") (pintype "passive"))
      (node (ref "u0") (pin "E6") (pinfunction "E6_E6") (pintype "passive"))
    )
    (net (code "62") (name "/PTE24") (class "Default")
      (node (ref "BT") (pin "4") (pinfunction "4_4") (pintype "passive"))
      (node (ref "u0") (pin "E24") (pinfunction "E24_E24") (pintype "passive"))
    )
    (net (code "63") (name "/PTE25") (class "Default")
      (node (ref "BT") (pin "3") (pinfunction "3_3") (pintype "passive"))
      (node (ref "u0") (pin "E25") (pinfunction "E25_E25") (pintype "passive"))
    )
    (net (code "64") (name "/PTE26") (class "Default")
      (node (ref "S0") (pin "4") (pinfunction "A4_4") (pintype "passive"))
      (node (ref "u0") (pin "E26") (pinfunction "E26_E26") (pintype "passive"))
    )
    (net (code "65") (name "3.3V_BUS") (class "Default")
      (node (ref "C22") (pin "2") (pinfunction "2_2") (pintype "passive"))
      (node (ref "C73") (pin "2") (pintype "passive"))
      (node (ref "POW2") (pin "5") (pinfunction "OUT_5") (pintype "passive"))
      (node (ref "R29") (pin "1") (pinfunction "1_1") (pintype "passive"))
      (node (ref "R30") (pin "1") (pinfunction "1_1") (pintype "passive"))
      (node (ref "R31") (pin "1") (pinfunction "1_1") (pintype "passive"))
      (node (ref "R32") (pin "1") (pinfunction "1_1") (pintype "passive"))
      (node (ref "U4") (pin "20") (pinfunction "VCC_20") (pintype "passive"))
    )
    (net (code "66") (name "3.3V_MCU") (class "Default")
      (node (ref "C1") (pin "1") (pinfunction "1_1") (pintype "passive"))
      (node (ref "C18") (pin "2") (pinfunction "2_2") (pintype "passive"))
      (node (ref "C2") (pin "1") (pinfunction "1_1") (pintype "passive"))
      (node (ref "C27") (pin "1") (pinfunction "VCC_1") (pintype "passive"))
      (node (ref "C3") (pin "2") (pinfunction "2_2") (pintype "passive"))
      (node (ref "C4") (pin "1") (pinfunction "1_1") (pintype "passive"))
      (node (ref "C61") (pin "2") (pinfunction "2_2") (pintype "passive"))
      (node (ref "Carmera") (pin "22") (pinfunction "22_22") (pintype "passive"))
      (node (ref "P1") (pin "2") (pinfunction "2_2") (pintype "passive"))
      (node (ref "P2") (pin "2") (pinfunction "2_2") (pintype "passive"))
      (node (ref "U6") (pin "8") (pinfunction "VCC1_8") (pintype "passive"))
      (node (ref "gyro") (pin "1") (pinfunction "1_1") (pintype "passive"))
      (node (ref "tps7333") (pin "5") (pinfunction "OUT_5") (pintype "passive"))
      (node (ref "tps7333") (pin "6") (pinfunction "OUT_6") (pintype "passive"))
      (node (ref "tps7333") (pin "7") (pinfunction "SENSE_7") (pintype "passive"))
      (node (ref "u0") (pin "3.3V") (pinfunction "3.3V_3.3V") (pintype "passive"))
    )
    (net (code "67") (name "5V_BUS") (class "Default")
      (node (ref "40_BUS") (pin "3") (pinfunction "out_3") (pintype "passive"))
      (node (ref "BT") (pin "1") (pinfunction "1_1") (pintype "passive"))
      (node (ref "C71") (pin "2") (pintype "passive"))
      (node (ref "POW2") (pin "1") (pinfunction "IN_1") (pintype "passive"))
      (node (ref "POW2") (pin "3") (pinfunction "EN_3") (pintype "passive"))
      (node (ref "TFT") (pin "15") (pinfunction "15_15") (pintype "passive"))
      (node (ref "beep") (pin "1") (pinfunction "A_1") (pintype "passive"))
      (node (ref "sonar1") (pin "1") (pinfunction "1_1") (pintype "passive"))
      (node (ref "sonar2") (pin "1") (pinfunction "1_1") (pintype "passive"))
    )
    (net (code "68") (name "Battery7.2") (class "Default")
      (node (ref "Main_Switch") (pin "1") (pinfunction "16_1") (pintype "passive"))
      (node (ref "T型头") (pin "2") (pinfunction "2_2") (pintype "passive"))
      (node (ref "总开关") (pin "1") (pinfunction "16_1") (pintype "passive"))
    )
    (net (code "69") (name "GND") (class "Default")
      (node (ref "C11") (pin "1") (pintype "passive"))
      (node (ref "C13") (pin "1") (pintype "passive"))
      (node (ref "C16") (pin "1") (pintype "passive"))
      (node (ref "C19") (pin "1") (pintype "passive"))
      (node (ref "C22") (pin "1") (pinfunction "1_1") (pintype "passive"))
      (node (ref "C5") (pin "2") (pinfunction "2_2") (pintype "passive"))
      (node (ref "C6") (pin "2") (pinfunction "2_2") (pintype "passive"))
      (node (ref "C7") (pin "2") (pinfunction "2_2") (pintype "passive"))
      (node (ref "C71") (pin "1") (pintype "passive"))
      (node (ref "C72") (pin "1") (pintype "passive"))
      (node (ref "C73") (pin "1") (pintype "passive"))
      (node (ref "POW2") (pin "2") (pinfunction "GND_2") (pintype "passive"))
      (node (ref "Q3") (pin "1") (pinfunction "D_1") (pintype "passive"))
      (node (ref "Q4") (pin "3") (pinfunction "S_3") (pintype "passive"))
      (node (ref "Q7") (pin "1") (pinfunction "D_1") (pintype "passive"))
      (node (ref "Q8") (pin "3") (pinfunction "S_3") (pintype "passive"))
      (node (ref "R16") (pin "1") (pinfunction "1_1") (pintype "passive"))
      (node (ref "R17") (pin "1") (pinfunction "1_1") (pintype "passive"))
      (node (ref "R18") (pin "2") (pinfunction "2_2") (pintype "passive"))
      (node (ref "R19") (pin "1") (pinfunction "1_1") (pintype "passive"))
      (node (ref "R26") (pin "1") (pinfunction "1_1") (pintype "passive"))
      (node (ref "R27") (pin "1") (pinfunction "1_1") (pintype "passive"))
      (node (ref "R28") (pin "2") (pinfunction "2_2") (pintype "passive"))
      (node (ref "R8") (pin "1") (pinfunction "1_1") (pintype "passive"))
      (node (ref "Rled2") (pin "2") (pintype "passive"))
      (node (ref "Ser") (pin "3") (pinfunction "3_3") (pintype "passive"))
      (node (ref "T型头") (pin "1") (pinfunction "1_1") (pintype "passive"))
      (node (ref "U1") (pin "2") (pinfunction "SB_2") (pintype "passive"))
      (node (ref "U1") (pin "4") (pinfunction "GND_4") (pintype "passive"))
      (node (ref "U2-1") (pin "6") (pinfunction "Vss_6") (pintype "passive"))
      (node (ref "U2-1") (pin "8") (pinfunction "DIS_8") (pintype "passive"))
      (node (ref "U2-2") (pin "6") (pinfunction "Vss_6") (pintype "passive"))
      (node (ref "U2-2") (pin "8") (pinfunction "DIS_8") (pintype "passive"))
      (node (ref "U4") (pin "1") (pinfunction "DIR_1") (pintype "passive"))
      (node (ref "U4") (pin "10") (pinfunction "GND_10") (pintype "passive"))
      (node (ref "U4") (pin "11") (pinfunction "B7_11") (pintype "passive"))
      (node (ref "U4") (pin "12") (pinfunction "B6_12") (pintype "passive"))
      (node (ref "U4") (pin "13") (pinfunction "B5_13") (pintype "passive"))
      (node (ref "U4") (pin "14") (pinfunction "B4_14") (pintype "passive"))
      (node (ref "U4") (pin "19") (pinfunction "~{OE}_19") (pintype "passive"))
      (node (ref "U4") (pin "6") (pinfunction "A4_6") (pintype "passive"))
      (node (ref "U4") (pin "7") (pinfunction "A5_7") (pintype "passive"))
      (node (ref "U4") (pin "8") (pinfunction "A6_8") (pintype "passive"))
      (node (ref "U4") (pin "9") (pinfunction "A7_9") (pintype "passive"))
    )
    (net (code "70") (name "GNDo") (class "Default")
      (node (ref "40_BUS") (pin "2") (pinfunction "GND_2") (pintype "passive"))
      (node (ref "BT") (pin "2") (pinfunction "2_2") (pintype "passive"))
      (node (ref "C1") (pin "2") (pinfunction "2_2") (pintype "passive"))
      (node (ref "C10") (pin "2") (pinfunction "2_2") (pintype "passive"))
      (node (ref "C12") (pin "1") (pinfunction "1_1") (pintype "passive"))
      (node (ref "C18") (pin "1") (pinfunction "1_1") (pintype "passive"))
      (node (ref "C2") (pin "2") (pinfunction "2_2") (pintype "passive"))
      (node (ref "C24") (pin "2") (pinfunction "GND_2") (pintype "passive"))
      (node (ref "C25") (pin "1") (pinfunction "1_1") (pintype "passive"))
      (node (ref "C27") (pin "2") (pinfunction "GND_2") (pintype "passive"))
      (node (ref "C3") (pin "1") (pinfunction "1_1") (pintype "passive"))
      (node (ref "C30") (pin "2") (pinfunction "2_2") (pintype "passive"))
      (node (ref "C4") (pin "2") (pinfunction "2_2") (pintype "passive"))
      (node (ref "C61") (pin "1") (pinfunction "1_1") (pintype "passive"))
      (node (ref "Carmera") (pin "21") (pinfunction "21_21") (pintype "passive"))
      (node (ref "Carmera") (pin "25") (pinfunction "MH1_25") (pintype "passive"))
      (node (ref "Carmera") (pin "26") (pinfunction "MH2_26") (pintype "passive"))
      (node (ref "P1") (pin "1") (pinfunction "1_1") (pintype "passive"))
      (node (ref "P2") (pin "1") (pinfunction "1_1") (pintype "passive"))
      (node (ref "Q9") (pin "3") (pinfunction "E_3") (pintype "passive"))
      (node (ref "R19") (pin "2") (pinfunction "2_2") (pintype "passive"))
      (node (ref "R3") (pin "2") (pintype "passive"))
      (node (ref "R5") (pin "1") (pintype "passive"))
      (node (ref "R6") (pin "2") (pintype "passive"))
      (node (ref "Rled1") (pin "2") (pintype "passive"))
      (node (ref "S0") (pin "10") (pinfunction "B7_10") (pintype "passive"))
      (node (ref "S0") (pin "11") (pinfunction "B6_11") (pintype "passive"))
      (node (ref "S0") (pin "12") (pinfunction "B5_12") (pintype "passive"))
      (node (ref "S0") (pin "13") (pinfunction "B4_13") (pintype "passive"))
      (node (ref "S0") (pin "14") (pinfunction "B3_14") (pintype "passive"))
      (node (ref "S0") (pin "15") (pinfunction "B2_15") (pintype "passive"))
      (node (ref "S0") (pin "16") (pinfunction "B1_16") (pintype "passive"))
      (node (ref "S0") (pin "9") (pinfunction "B8_9") (pintype "passive"))
      (node (ref "S1") (pin "1") (pinfunction "1_1") (pintype "passive"))
      (node (ref "S2") (pin "1") (pinfunction "1_1") (pintype "passive"))
      (node (ref "S3") (pin "1") (pinfunction "1_1") (pintype "passive"))
      (node (ref "S4") (pin "1") (pinfunction "1_1") (pintype "passive"))
      (node (ref "S5") (pin "1") (pinfunction "1_1") (pintype "passive"))
      (node (ref "S6") (pin "1") (pinfunction "1_1") (pintype "passive"))
      (node (ref "S7") (pin "5") (pinfunction "B4_5") (pintype "passive"))
      (node (ref "S7") (pin "6") (pinfunction "B3_6") (pintype "passive"))
      (node (ref "S7") (pin "7") (pinfunction "B2_7") (pintype "passive"))
      (node (ref "S7") (pin "8") (pinfunction "B1_8") (pintype "passive"))
      (node (ref "TFT") (pin "16") (pinfunction "16_16") (pintype "passive"))
      (node (ref "U6") (pin "1") (pinfunction "A0_1") (pintype "passive"))
      (node (ref "U6") (pin "2") (pinfunction "A1_2") (pintype "passive"))
      (node (ref "U6") (pin "3") (pinfunction "A2_3") (pintype "passive"))
      (node (ref "U6") (pin "4") (pinfunction "GND_4") (pintype "passive"))
      (node (ref "U6") (pin "7") (pinfunction "WP_7") (pintype "passive"))
      (node (ref "gyro") (pin "4") (pinfunction "4_4") (pintype "passive"))
      (node (ref "sonar1") (pin "2") (pinfunction "2_2") (pintype "passive"))
      (node (ref "sonar2") (pin "2") (pinfunction "2_2") (pintype "passive"))
      (node (ref "tps7333") (pin "1") (pinfunction "GND_1") (pintype "passive"))
      (node (ref "tps7333") (pin "2") (pinfunction "~{EN}_2") (pintype "passive"))
      (node (ref "u0") (pin "GND") (pinfunction "GND_GND") (pintype "passive"))
    )
    (net (code "71") (name "Main_7.2") (class "Default")
      (node (ref "40_BUS") (pin "1") (pinfunction "input_1") (pintype "passive"))
      (node (ref "C10") (pin "1") (pinfunction "1_1") (pintype "passive"))
      (node (ref "C12") (pin "2") (pinfunction "2_2") (pintype "passive"))
      (node (ref "C24") (pin "1") (pinfunction "VCC_1") (pintype "passive"))
      (node (ref "C25") (pin "2") (pinfunction "2_2") (pintype "passive"))
      (node (ref "C30") (pin "1") (pinfunction "1_1") (pintype "passive"))
      (node (ref "LED1") (pin "1") (pinfunction "A_1") (pintype "passive"))
      (node (ref "Main_Switch") (pin "2") (pinfunction "17_2") (pintype "passive"))
      (node (ref "Main_Switch") (pin "3") (pinfunction "18_3") (pintype "passive"))
      (node (ref "Ser") (pin "2") (pinfunction "2_2") (pintype "passive"))
      (node (ref "tps7333") (pin "3") (pinfunction "Vin_3") (pintype "passive"))
      (node (ref "tps7333") (pin "4") (pinfunction "Vin_4") (pintype "passive"))
    )
    (net (code "72") (name "Net-(D1-A)") (class "Default")
      (node (ref "D1") (pin "1") (pinfunction "A_1") (pintype "passive"))
      (node (ref "L1") (pin "2") (pinfunction "2_2") (pintype "passive"))
      (node (ref "U1") (pin "1") (pinfunction "SC_1") (pintype "passive"))
    )
    (net (code "73") (name "Net-(D2-K)") (class "Default")
      (node (ref "C14") (pin "2") (pinfunction "2_2") (pintype "passive"))
      (node (ref "D2") (pin "2") (pinfunction "K_2") (pintype "passive"))
      (node (ref "U2-1") (pin "1") (pinfunction "BHB_1") (pintype "passive"))
    )
    (net (code "74") (name "Net-(D3-K)") (class "Default")
      (node (ref "C15") (pin "2") (pinfunction "2_2") (pintype "passive"))
      (node (ref "D3") (pin "2") (pinfunction "K_2") (pintype "passive"))
      (node (ref "U2-1") (pin "9") (pinfunction "AHB_9") (pintype "passive"))
    )
    (net (code "75") (name "Net-(D4-K)") (class "Default")
      (node (ref "C20") (pin "2") (pinfunction "2_2") (pintype "passive"))
      (node (ref "D4") (pin "2") (pinfunction "K_2") (pintype "passive"))
      (node (ref "U2-2") (pin "1") (pinfunction "BHB_1") (pintype "passive"))
    )
    (net (code "76") (name "Net-(D5-K)") (class "Default")
      (node (ref "C21") (pin "2") (pinfunction "2_2") (pintype "passive"))
      (node (ref "D5") (pin "2") (pinfunction "K_2") (pintype "passive"))
      (node (ref "U2-2") (pin "9") (pinfunction "AHB_9") (pintype "passive"))
    )
    (net (code "77") (name "Net-(LED1-K)") (class "Default")
      (node (ref "LED1") (pin "2") (pinfunction "K_2") (pintype "passive"))
      (node (ref "Rled1") (pin "1") (pintype "passive"))
    )
    (net (code "78") (name "Net-(LED2-K)") (class "Default")
      (node (ref "LED2") (pin "2") (pinfunction "K_2") (pintype "passive"))
      (node (ref "Rled2") (pin "1") (pintype "passive"))
    )
    (net (code "79") (name "Net-(POW2-BP)") (class "Default")
      (node (ref "C72") (pin "2") (pintype "passive"))
      (node (ref "POW2") (pin "4") (pinfunction "BP_4") (pintype "passive"))
    )
    (net (code "80") (name "Net-(Q1-D)") (class "Default")
      (node (ref "C15") (pin "1") (pinfunction "1_1") (pintype "passive"))
      (node (ref "Q1") (pin "1") (pinfunction "D_1") (pintype "passive"))
      (node (ref "Q3") (pin "3") (pinfunction "S_3") (pintype "passive"))
      (node (ref "R12") (pin "1") (pinfunction "1_1") (pintype "passive"))
      (node (ref "U2-1") (pin "11") (pinfunction "AHS_11") (pintype "passive"))
    )
    (net (code "81") (name "Net-(Q1-G)") (class "Default")
      (node (ref "Q1") (pin "2") (pinfunction "G_2") (pintype "passive"))
      (node (ref "R10") (pin "1") (pinfunction "1_1") (pintype "passive"))
      (node (ref "R12") (pin "2") (pinfunction "2_2") (pintype "passive"))
    )
    (net (code "82") (name "Net-(Q2-G)") (class "Default")
      (node (ref "Q2") (pin "2") (pinfunction "G_2") (pintype "passive"))
      (node (ref "R11") (pin "2") (pinfunction "2_2") (pintype "passive"))
      (node (ref "R13") (pin "2") (pinfunction "2_2") (pintype "passive"))
    )
    (net (code "83") (name "Net-(Q2-S)") (class "Default")
      (node (ref "C14") (pin "1") (pinfunction "1_1") (pintype "passive"))
      (node (ref "Q2") (pin "3") (pinfunction "S_3") (pintype "passive"))
      (node (ref "Q4") (pin "1") (pinfunction "D_1") (pintype "passive"))
      (node (ref "R13") (pin "1") (pinfunction "1_1") (pintype "passive"))
      (node (ref "U2-1") (pin "15") (pinfunction "BHS_15") (pintype "passive"))
    )
    (net (code "84") (name "Net-(Q3-G)") (class "Default")
      (node (ref "Q3") (pin "2") (pinfunction "G_2") (pintype "passive"))
      (node (ref "R14") (pin "1") (pinfunction "1_1") (pintype "passive"))
      (node (ref "R16") (pin "2") (pinfunction "2_2") (pintype "passive"))
    )
    (net (code "85") (name "Net-(Q4-G)") (class "Default")
      (node (ref "Q4") (pin "2") (pinfunction "G_2") (pintype "passive"))
      (node (ref "R15") (pin "2") (pinfunction "2_2") (pintype "passive"))
      (node (ref "R17") (pin "2") (pinfunction "2_2") (pintype "passive"))
    )
    (net (code "86") (name "Net-(Q5-D)") (class "Default")
      (node (ref "C21") (pin "1") (pinfunction "1_1") (pintype "passive"))
      (node (ref "Q5") (pin "1") (pinfunction "D_1") (pintype "passive"))
      (node (ref "Q7") (pin "3") (pinfunction "S_3") (pintype "passive"))
      (node (ref "R22") (pin "1") (pinfunction "1_1") (pintype "passive"))
      (node (ref "U2-2") (pin "11") (pinfunction "AHS_11") (pintype "passive"))
    )
    (net (code "87") (name "Net-(Q5-G)") (class "Default")
      (node (ref "Q5") (pin "2") (pinfunction "G_2") (pintype "passive"))
      (node (ref "R20") (pin "1") (pinfunction "1_1") (pintype "passive"))
      (node (ref "R22") (pin "2") (pinfunction "2_2") (pintype "passive"))
    )
    (net (code "88") (name "Net-(Q6-G)") (class "Default")
      (node (ref "Q6") (pin "2") (pinfunction "G_2") (pintype "passive"))
      (node (ref "R21") (pin "2") (pinfunction "2_2") (pintype "passive"))
      (node (ref "R23") (pin "2") (pinfunction "2_2") (pintype "passive"))
    )
    (net (code "89") (name "Net-(Q6-S)") (class "Default")
      (node (ref "C20") (pin "1") (pinfunction "1_1") (pintype "passive"))
      (node (ref "Q6") (pin "3") (pinfunction "S_3") (pintype "passive"))
      (node (ref "Q8") (pin "1") (pinfunction "D_1") (pintype "passive"))
      (node (ref "R23") (pin "1") (pinfunction "1_1") (pintype "passive"))
      (node (ref "U2-2") (pin "15") (pinfunction "BHS_15") (pintype "passive"))
    )
    (net (code "90") (name "Net-(Q7-G)") (class "Default")
      (node (ref "Q7") (pin "2") (pinfunction "G_2") (pintype "passive"))
      (node (ref "R24") (pin "1") (pinfunction "1_1") (pintype "passive"))
      (node (ref "R26") (pin "2") (pinfunction "2_2") (pintype "passive"))
    )
    (net (code "91") (name "Net-(Q8-G)") (class "Default")
      (node (ref "Q8") (pin "2") (pinfunction "G_2") (pintype "passive"))
      (node (ref "R25") (pin "2") (pinfunction "2_2") (pintype "passive"))
      (node (ref "R27") (pin "2") (pinfunction "2_2") (pintype "passive"))
    )
    (net (code "92") (name "Net-(Q9-B)") (class "Default")
      (node (ref "Q9") (pin "2") (pinfunction "B_2") (pintype "passive"))
      (node (ref "R1") (pin "2") (pintype "passive"))
      (node (ref "R5") (pin "2") (pintype "passive"))
    )
    (net (code "93") (name "Net-(Q9-C)") (class "Default")
      (node (ref "Q9") (pin "1") (pinfunction "C_1") (pintype "passive"))
      (node (ref "beep") (pin "2") (pinfunction "B_2") (pintype "passive"))
    )
    (net (code "94") (name "Net-(U1-DRI)") (class "Default")
      (node (ref "R4") (pin "1") (pinfunction "1_1") (pintype "passive"))
      (node (ref "U1") (pin "8") (pinfunction "DRI_8") (pintype "passive"))
    )
    (net (code "95") (name "Net-(U1-FB)") (class "Default")
      (node (ref "R7") (pin "2") (pinfunction "2_2") (pintype "passive"))
      (node (ref "R8") (pin "2") (pinfunction "2_2") (pintype "passive"))
      (node (ref "U1") (pin "5") (pinfunction "FB_5") (pintype "passive"))
    )
    (net (code "96") (name "Net-(U1-IPK)") (class "Default")
      (node (ref "L1") (pin "1") (pinfunction "1_1") (pintype "passive"))
      (node (ref "R2") (pin "2") (pinfunction "2_2") (pintype "passive"))
      (node (ref "R4") (pin "2") (pinfunction "2_2") (pintype "passive"))
      (node (ref "U1") (pin "7") (pinfunction "IPK_7") (pintype "passive"))
    )
    (net (code "97") (name "Net-(U1-TC)") (class "Default")
      (node (ref "C6") (pin "1") (pinfunction "1_1") (pintype "passive"))
      (node (ref "U1") (pin "3") (pinfunction "TC_3") (pintype "passive"))
    )
    (net (code "98") (name "Net-(U2-1-AHO)") (class "Default")
      (node (ref "R10") (pin "2") (pinfunction "2_2") (pintype "passive"))
      (node (ref "U2-1") (pin "10") (pinfunction "AHO_10") (pintype "passive"))
    )
    (net (code "99") (name "Net-(U2-1-ALO)") (class "Default")
      (node (ref "R14") (pin "2") (pinfunction "2_2") (pintype "passive"))
      (node (ref "U2-1") (pin "13") (pinfunction "ALO_13") (pintype "passive"))
    )
    (net (code "100") (name "Net-(U2-1-BHO)") (class "Default")
      (node (ref "R11") (pin "1") (pinfunction "1_1") (pintype "passive"))
      (node (ref "U2-1") (pin "16") (pinfunction "BHO_16") (pintype "passive"))
    )
    (net (code "101") (name "Net-(U2-1-BLO)") (class "Default")
      (node (ref "R15") (pin "1") (pinfunction "1_1") (pintype "passive"))
      (node (ref "U2-1") (pin "14") (pinfunction "BLO_14") (pintype "passive"))
    )
    (net (code "102") (name "Net-(U2-1-DEL)") (class "Default")
      (node (ref "R18") (pin "1") (pinfunction "1_1") (pintype "passive"))
      (node (ref "U2-1") (pin "5") (pinfunction "DEL_5") (pintype "passive"))
    )
    (net (code "103") (name "Net-(U2-2-AHO)") (class "Default")
      (node (ref "R20") (pin "2") (pinfunction "2_2") (pintype "passive"))
      (node (ref "U2-2") (pin "10") (pinfunction "AHO_10") (pintype "passive"))
    )
    (net (code "104") (name "Net-(U2-2-ALO)") (class "Default")
      (node (ref "R24") (pin "2") (pinfunction "2_2") (pintype "passive"))
      (node (ref "U2-2") (pin "13") (pinfunction "ALO_13") (pintype "passive"))
    )
    (net (code "105") (name "Net-(U2-2-BHO)") (class "Default")
      (node (ref "R21") (pin "1") (pinfunction "1_1") (pintype "passive"))
      (node (ref "U2-2") (pin "16") (pinfunction "BHO_16") (pintype "passive"))
    )
    (net (code "106") (name "Net-(U2-2-BLO)") (class "Default")
      (node (ref "R25") (pin "1") (pinfunction "1_1") (pintype "passive"))
      (node (ref "U2-2") (pin "14") (pinfunction "BLO_14") (pintype "passive"))
    )
    (net (code "107") (name "Net-(U2-2-DEL)") (class "Default")
      (node (ref "R28") (pin "1") (pinfunction "1_1") (pintype "passive"))
      (node (ref "U2-2") (pin "5") (pinfunction "DEL_5") (pintype "passive"))
    )
    (net (code "108") (name "Switch_7.2") (class "Default")
      (node (ref "C7") (pin "1") (pinfunction "1_1") (pintype "passive"))
      (node (ref "LED2") (pin "1") (pinfunction "A_1") (pintype "passive"))
      (node (ref "Q1") (pin "3") (pinfunction "S_3") (pintype "passive"))
      (node (ref "Q2") (pin "1") (pinfunction "D_1") (pintype "passive"))
      (node (ref "Q5") (pin "3") (pinfunction "S_3") (pintype "passive"))
      (node (ref "Q6") (pin "1") (pinfunction "D_1") (pintype "passive"))
      (node (ref "R2") (pin "1") (pinfunction "1_1") (pintype "passive"))
      (node (ref "U1") (pin "6") (pinfunction "VCC_6") (pintype "passive"))
      (node (ref "总开关") (pin "2") (pinfunction "17_2") (pintype "passive"))
      (node (ref "总开关") (pin "3") (pinfunction "18_3") (pintype "passive"))
    )
    (net (code "109") (name "VCC20") (class "Default")
      (node (ref "C11") (pin "2") (pintype "passive"))
      (node (ref "C13") (pin "2") (pintype "passive"))
      (node (ref "C16") (pin "2") (pintype "passive"))
      (node (ref "C19") (pin "2") (pintype "passive"))
      (node (ref "C5") (pin "1") (pinfunction "1_1") (pintype "passive"))
      (node (ref "D1") (pin "2") (pinfunction "K_2") (pintype "passive"))
      (node (ref "D2") (pin "1") (pinfunction "A_1") (pintype "passive"))
      (node (ref "D3") (pin "1") (pinfunction "A_1") (pintype "passive"))
      (node (ref "D4") (pin "1") (pinfunction "A_1") (pintype "passive"))
      (node (ref "D5") (pin "1") (pinfunction "A_1") (pintype "passive"))
      (node (ref "R7") (pin "1") (pinfunction "1_1") (pintype "passive"))
      (node (ref "U2-1") (pin "12") (pinfunction "Vdd_12") (pintype "passive"))
      (node (ref "U2-1") (pin "2") (pinfunction "BHI_2") (pintype "passive"))
      (node (ref "U2-1") (pin "7") (pinfunction "AHI_7") (pintype "passive"))
      (node (ref "U2-2") (pin "12") (pinfunction "Vdd_12") (pintype "passive"))
      (node (ref "U2-2") (pin "2") (pinfunction "BHI_2") (pintype "passive"))
      (node (ref "U2-2") (pin "7") (pinfunction "AHI_7") (pintype "passive"))
    )
    (net (code "110") (name "unconnected-(40_BUS-GND-Pad4)") (class "Default")
      (node (ref "40_BUS") (pin "4") (pinfunction "GND_4") (pintype "passive"))
    )
    (net (code "111") (name "unconnected-(Carmera-Pad1)") (class "Default")
      (node (ref "Carmera") (pin "1") (pinfunction "1_1") (pintype "passive+no_connect"))
    )
    (net (code "112") (name "unconnected-(Carmera-Pad2)") (class "Default")
      (node (ref "Carmera") (pin "2") (pinfunction "2_2") (pintype "passive+no_connect"))
    )
    (net (code "113") (name "unconnected-(Carmera-Pad3)") (class "Default")
      (node (ref "Carmera") (pin "3") (pinfunction "3_3") (pintype "passive+no_connect"))
    )
    (net (code "114") (name "unconnected-(Carmera-Pad5)") (class "Default")
      (node (ref "Carmera") (pin "5") (pinfunction "5_5") (pintype "passive+no_connect"))
    )
    (net (code "115") (name "unconnected-(Carmera-Pad7)") (class "Default")
      (node (ref "Carmera") (pin "7") (pinfunction "7_7") (pintype "passive+no_connect"))
    )
    (net (code "116") (name "unconnected-(Carmera-Pad8)") (class "Default")
      (node (ref "Carmera") (pin "8") (pinfunction "8_8") (pintype "passive+no_connect"))
    )
    (net (code "117") (name "unconnected-(Carmera-Pad9)") (class "Default")
      (node (ref "Carmera") (pin "9") (pinfunction "9_9") (pintype "passive+no_connect"))
    )
    (net (code "118") (name "unconnected-(Carmera-Pad10)") (class "Default")
      (node (ref "Carmera") (pin "10") (pinfunction "10_10") (pintype "passive+no_connect"))
    )
    (net (code "119") (name "unconnected-(Carmera-Pad23)") (class "Default")
      (node (ref "Carmera") (pin "23") (pinfunction "23_23") (pintype "passive+no_connect"))
    )
    (net (code "120") (name "unconnected-(Carmera-Pad24)") (class "Default")
      (node (ref "Carmera") (pin "24") (pinfunction "24_24") (pintype "passive+no_connect"))
    )
    (net (code "121") (name "unconnected-(TFT-Pad14)") (class "Default")
      (node (ref "TFT") (pin "14") (pinfunction "14_14") (pintype "passive+no_connect"))
    )
    (net (code "122") (name "unconnected-(sonar1-Pad4)") (class "Default")
      (node (ref "sonar1") (pin "4") (pinfunction "4_4") (pintype "passive"))
    )
    (net (code "123") (name "unconnected-(sonar2-Pad4)") (class "Default")
      (node (ref "sonar2") (pin "4") (pinfunction "4_4") (pintype "passive"))
    )
    (net (code "124") (name "unconnected-(tps7333-~{RE}-Pad8)") (class "Default")
      (node (ref "tps7333") (pin "8") (pinfunction "~{RE}_8") (pintype "passive"))
    )
    (net (code "125") (name "unconnected-(u0-PadA0)") (class "Default")
      (node (ref "u0") (pin "A0") (pinfunction "A0_A0") (pintype "passive+no_connect"))
    )
    (net (code "126") (name "unconnected-(u0-PadA0M3)") (class "Default")
      (node (ref "u0") (pin "A0M3") (pinfunction "A0M3_A0M3") (pintype "passive"))
    )
    (net (code "127") (name "unconnected-(u0-PadA0P3)") (class "Default")
      (node (ref "u0") (pin "A0P3") (pinfunction "A0P3_A0P3") (pintype "passive"))
    )
    (net (code "128") (name "unconnected-(u0-PadA1)") (class "Default")
      (node (ref "u0") (pin "A1") (pinfunction "A1_A1") (pintype "passive+no_connect"))
    )
    (net (code "129") (name "unconnected-(u0-PadA1M3)") (class "Default")
      (node (ref "u0") (pin "A1M3") (pinfunction "A1M3_A1M3") (pintype "passive"))
    )
    (net (code "130") (name "unconnected-(u0-PadA1P3)") (class "Default")
      (node (ref "u0") (pin "A1P3") (pinfunction "A1P3_A1P3") (pintype "passive"))
    )
    (net (code "131") (name "unconnected-(u0-PadA2)") (class "Default")
      (node (ref "u0") (pin "A2") (pinfunction "A2_A2") (pintype "passive+no_connect"))
    )
    (net (code "132") (name "unconnected-(u0-PadA3)") (class "Default")
      (node (ref "u0") (pin "A3") (pinfunction "A3_A3") (pintype "passive+no_connect"))
    )
    (net (code "133") (name "unconnected-(u0-PadA4)") (class "Default")
      (node (ref "u0") (pin "A4") (pinfunction "A4_A4") (pintype "passive+no_connect"))
    )
    (net (code "134") (name "unconnected-(u0-PadADC0_DM1)") (class "Default")
      (node (ref "u0") (pin "ADC0_DM1") (pinfunction "ADC0_DM1_ADC0_DM1") (pintype "passive"))
    )
    (net (code "135") (name "unconnected-(u0-PadADC0_DP1)") (class "Default")
      (node (ref "u0") (pin "ADC0_DP1") (pinfunction "ADC0_DP1_ADC0_DP1") (pintype "passive"))
    )
    (net (code "136") (name "unconnected-(u0-PadADC1_DM1)") (class "Default")
      (node (ref "u0") (pin "ADC1_DM1") (pinfunction "ADC1_DM1_ADC1_DM1") (pintype "passive"))
    )
    (net (code "137") (name "unconnected-(u0-PadADC1_DP1)") (class "Default")
      (node (ref "u0") (pin "ADC1_DP1") (pinfunction "ADC1_DP1_ADC1_DP1") (pintype "passive"))
    )
    (net (code "138") (name "unconnected-(u0-PadRESET_B)") (class "Default")
      (node (ref "u0") (pin "RESET_B") (pinfunction "RESET_B_RESET_B") (pintype "passive"))
    )
    (net (code "139") (name "unconnected-(u0-PadUSB0_DM)") (class "Default")
      (node (ref "u0") (pin "USB0_DM") (pinfunction "USB0_DM_USB0_DM") (pintype "passive"))
    )
    (net (code "140") (name "unconnected-(u0-PadUSB0_DP)") (class "Default")
      (node (ref "u0") (pin "USB0_DP") (pinfunction "USB0_DP_USB0_DP") (pintype "passive"))
    )
  )
)
